# RadioSignalBlocker.net
KiCad netlist of a schematic drawn in Altium Designer
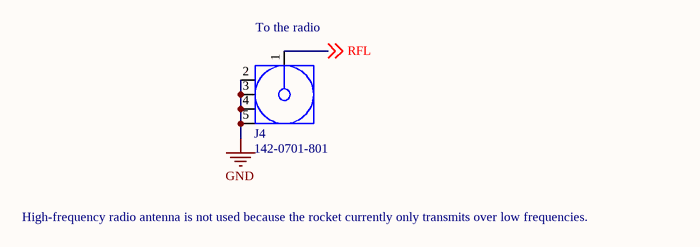
[diagram p0: RadioSignalBlocker.SchDoc]

(export (version "E")
  (design (tool "Eeschema 10.0.6"))
  (components
    (comp (ref "J4")
      (value "142-0701-801")
      (footprint "CINC-142-0701-801_V")
      (description "SMA End Launch Jack Receptacle, 50 Ohm, 0 to 18 GHz, -65 to 165 degC, 5-Pin SMD, RoHS, Bulk")
      (fields (field (name "MANUFACTURER") "EmersonConnectivitySolutions"))
      (libsource (lib "Altium Content Vault") (part "CN-S-4F-RF5"))
    )
  )
  (nets
    (net (code "1") (name "GND") (class "Default")
      (node (ref "J4") (pin "2") (pinfunction "2_2") (pintype "passive"))
      (node (ref "J4") (pin "3") (pinfunction "3_3") (pintype "passive"))
      (node (ref "J4") (pin "4") (pinfunction "4_4") (pintype "passive"))
      (node (ref "J4") (pin "5") (pinfunction "5_5") (pintype "passive"))
    )
    (net (code "2") (name "RFL") (class "Default")
      (node (ref "J4") (pin "1") (pinfunction "1_1") (pintype "passive"))
    )
  )
)
